# demo.net
KiCad netlist of a schematic drawn in Altium Designer
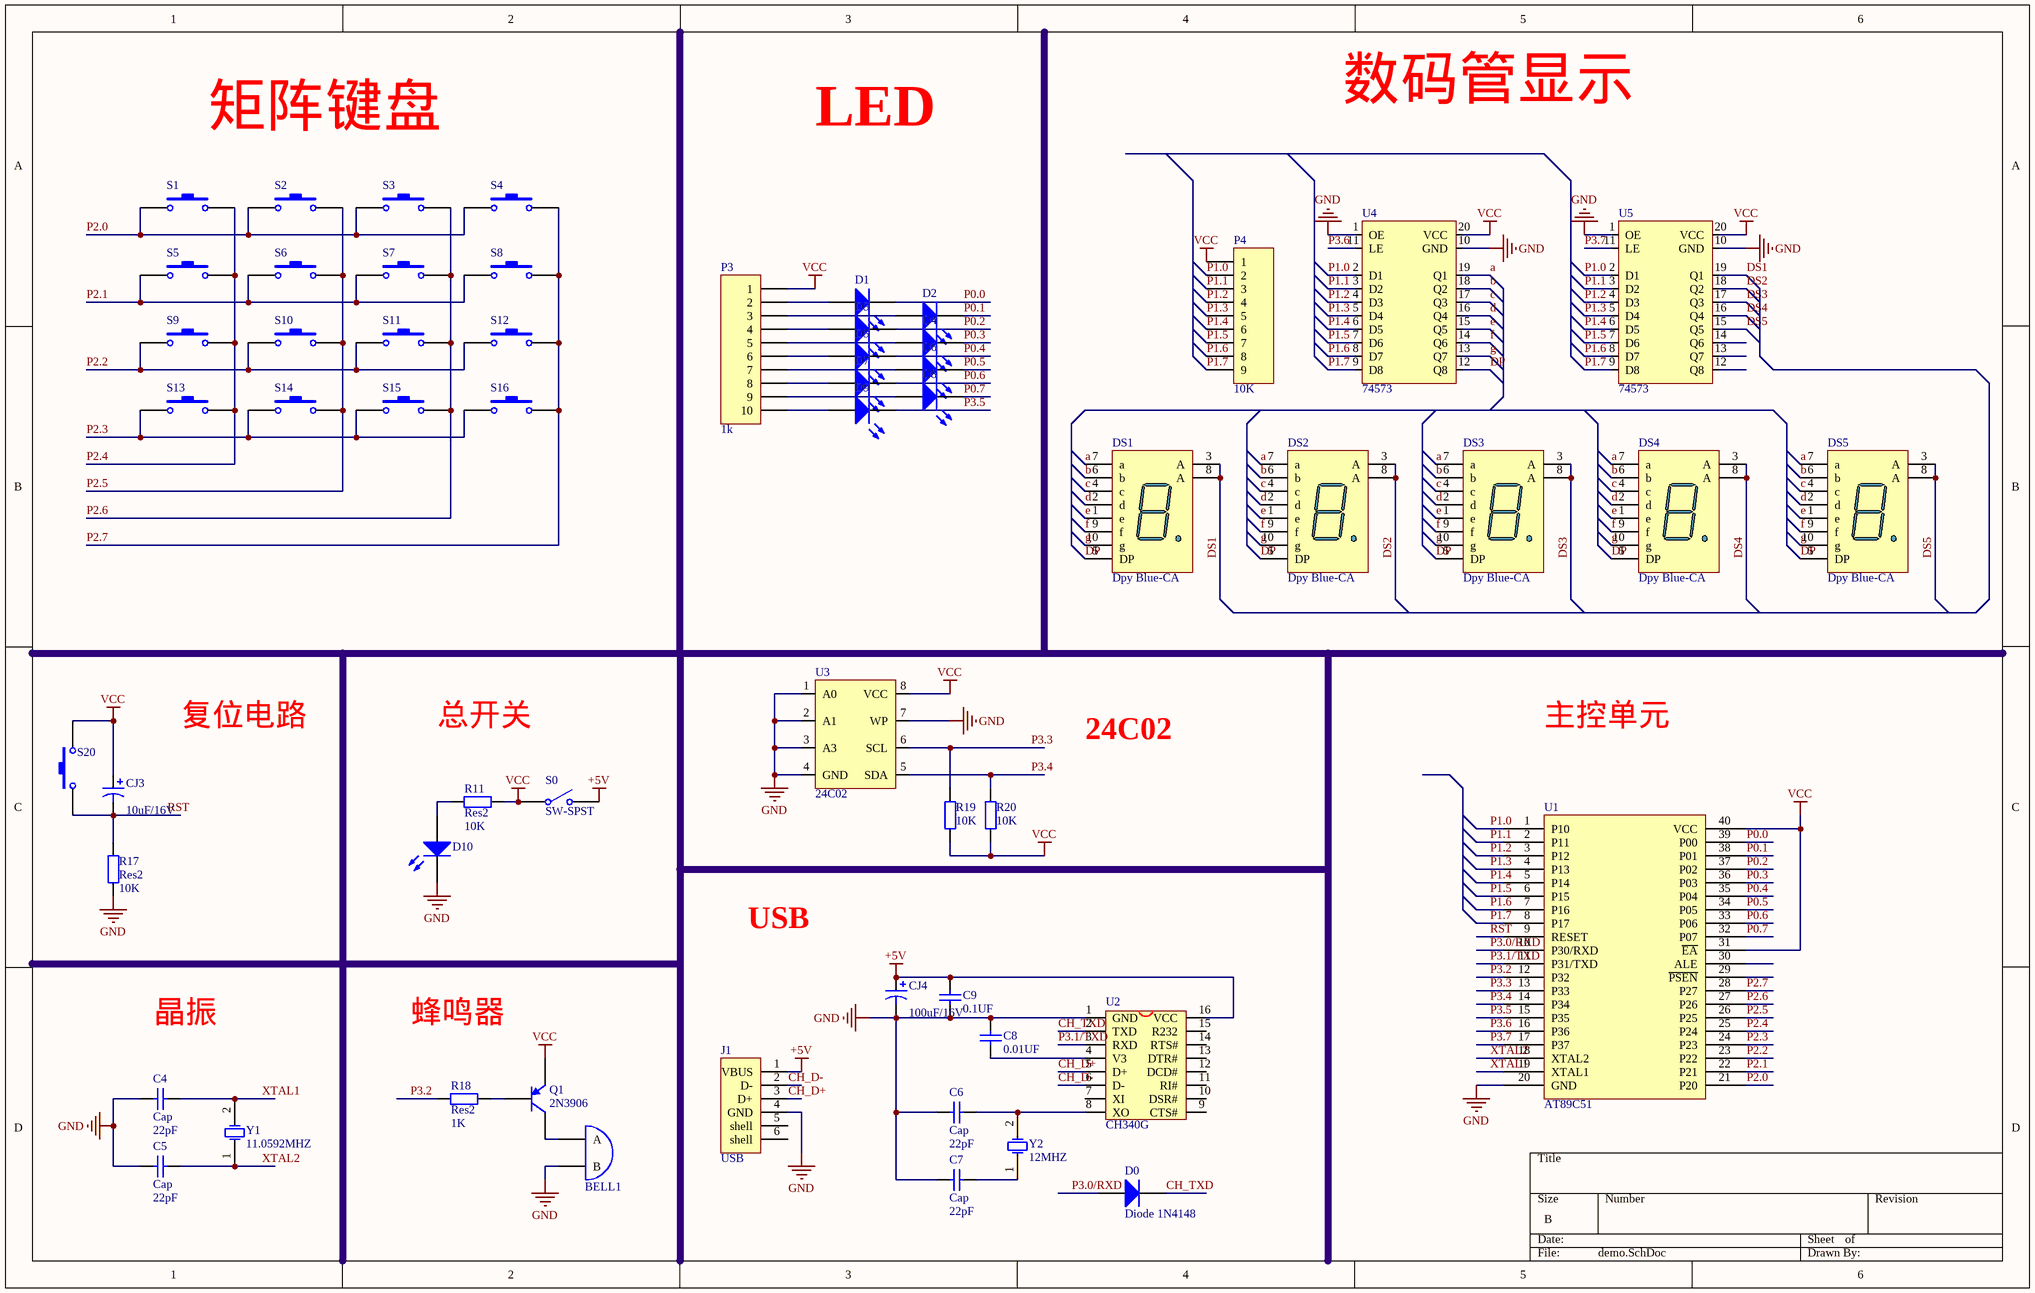
[diagram p0: demo.SchDoc]

(export (version "E")
  (design (tool "Eeschema 10.0.6"))
  (components
    (comp (ref "BELL1") (value "BELL") (footprint "BELL") (libsource (lib "SQ-1") (part "BELL")))
    (comp (ref "C4")
      (value "Cap")
      (footprint "0805C")
      (description "Capacitor")
      (fields (field (name "ALTIUM_VALUE") "22pF") (field (name "PUBLISHER") "Altium Limited"))
      (libsource (lib "Miscellaneous Devices") (part "Cap"))
    )
    (comp (ref "C5")
      (value "Cap")
      (footprint "0805C")
      (description "Capacitor")
      (fields (field (name "ALTIUM_VALUE") "22pF") (field (name "PUBLISHER") "Altium Limited"))
      (libsource (lib "Miscellaneous Devices") (part "Cap"))
    )
    (comp (ref "C6")
      (value "Cap")
      (footprint "0805C")
      (description "Capacitor")
      (fields (field (name "ALTIUM_VALUE") "22pF") (field (name "PUBLISHER") "Altium Limited"))
      (libsource (lib "Miscellaneous Devices") (part "Cap"))
    )
    (comp (ref "C7")
      (value "Cap")
      (footprint "0805C")
      (description "Capacitor")
      (fields (field (name "ALTIUM_VALUE") "22pF") (field (name "PUBLISHER") "Altium Limited"))
      (libsource (lib "Miscellaneous Devices") (part "Cap"))
    )
    (comp (ref "C8")
      (value "0.01UF")
      (footprint "0805C")
      (description "Capacitor")
      (fields (field (name "PUBLISHER") "Altium Limited"))
      (libsource (lib "Miscellaneous Devices") (part "Cap"))
    )
    (comp (ref "C9")
      (value "0.1UF")
      (footprint "0805C")
      (description "Capacitor")
      (fields (field (name "PUBLISHER") "Altium Limited"))
      (libsource (lib "Miscellaneous Devices") (part "Cap"))
    )
    (comp (ref "CJ3")
      (value "10uF/16V")
      (footprint "RB10U")
      (description "Polarized Capacitor (Radial)")
      (fields (field (name "PUBLISHER") "Altium Limited"))
      (libsource (lib "Miscellaneous Devices") (part "Cap Pol1"))
    )
    (comp (ref "CJ4")
      (value "100uF/16V")
      (footprint "RB10U")
      (description "Polarized Capacitor (Radial)")
      (fields (field (name "PUBLISHER") "Altium Limited"))
      (libsource (lib "Miscellaneous Devices") (part "Cap Pol1"))
    )
    (comp (ref "D0")
      (value "Diode 1N4148")
      (footprint "SOD123F")
      (description "High Conductance Fast Diode")
      (fields (field (name "PUBLISHER") "Altium Limited"))
      (libsource (lib "SQ-1") (part "Diode 1N4148"))
    )
    (comp (ref "D1")
      (value "LED0")
      (footprint "0805-LED")
      (description "Typical INFRARED GaAs LED")
      (fields (field (name "PUBLISHER") "Altium Limited"))
      (libsource (lib "Miscellaneous Devices") (part "LED0"))
    )
    (comp (ref "D2")
      (value "LED0")
      (footprint "0805-LED")
      (description "Typical INFRARED GaAs LED")
      (fields (field (name "PUBLISHER") "Altium Limited"))
      (libsource (lib "Miscellaneous Devices") (part "LED0"))
    )
    (comp (ref "D3")
      (value "LED0")
      (footprint "0805-LED")
      (description "Typical INFRARED GaAs LED")
      (fields (field (name "PUBLISHER") "Altium Limited"))
      (libsource (lib "Miscellaneous Devices") (part "LED0"))
    )
    (comp (ref "D4")
      (value "LED0")
      (footprint "0805-LED")
      (description "Typical INFRARED GaAs LED")
      (fields (field (name "PUBLISHER") "Altium Limited"))
      (libsource (lib "Miscellaneous Devices") (part "LED0"))
    )
    (comp (ref "D5")
      (value "LED0")
      (footprint "0805-LED")
      (description "Typical INFRARED GaAs LED")
      (fields (field (name "PUBLISHER") "Altium Limited"))
      (libsource (lib "Miscellaneous Devices") (part "LED0"))
    )
    (comp (ref "D6")
      (value "LED0")
      (footprint "0805-LED")
      (description "Typical INFRARED GaAs LED")
      (fields (field (name "PUBLISHER") "Altium Limited"))
      (libsource (lib "Miscellaneous Devices") (part "LED0"))
    )
    (comp (ref "D7")
      (value "LED0")
      (footprint "0805-LED")
      (description "Typical INFRARED GaAs LED")
      (fields (field (name "PUBLISHER") "Altium Limited"))
      (libsource (lib "Miscellaneous Devices") (part "LED0"))
    )
    (comp (ref "D8")
      (value "LED0")
      (footprint "0805-LED")
      (description "Typical INFRARED GaAs LED")
      (fields (field (name "PUBLISHER") "Altium Limited"))
      (libsource (lib "Miscellaneous Devices") (part "LED0"))
    )
    (comp (ref "D9")
      (value "LED0")
      (footprint "0805-LED")
      (description "Typical INFRARED GaAs LED")
      (fields (field (name "PUBLISHER") "Altium Limited"))
      (libsource (lib "Miscellaneous Devices") (part "LED0"))
    )
    (comp (ref "D10")
      (value "LED0")
      (footprint "0805-LED")
      (description "Typical INFRARED GaAs LED")
      (fields (field (name "PUBLISHER") "Altium Limited"))
      (libsource (lib "Miscellaneous Devices") (part "LED0"))
    )
    (comp (ref "DS1")
      (value "Dpy Blue-CA")
      (footprint "H")
      (description "14.2 mm General Purpose Blue 7-Segment Display: CA, RH DP, Gray Surface")
      (fields (field (name "PUBLISHER") "Altium Limited"))
      (libsource (lib "Miscellaneous Devices") (part "Dpy Blue-CA"))
    )
    (comp (ref "DS2")
      (value "Dpy Blue-CA")
      (footprint "H")
      (description "14.2 mm General Purpose Blue 7-Segment Display: CA, RH DP, Gray Surface")
      (fields (field (name "PUBLISHER") "Altium Limited"))
      (libsource (lib "Miscellaneous Devices") (part "Dpy Blue-CA"))
    )
    (comp (ref "DS3")
      (value "Dpy Blue-CA")
      (footprint "H")
      (description "14.2 mm General Purpose Blue 7-Segment Display: CA, RH DP, Gray Surface")
      (fields (field (name "PUBLISHER") "Altium Limited"))
      (libsource (lib "Miscellaneous Devices") (part "Dpy Blue-CA"))
    )
    (comp (ref "DS4")
      (value "Dpy Blue-CA")
      (footprint "H")
      (description "14.2 mm General Purpose Blue 7-Segment Display: CA, RH DP, Gray Surface")
      (fields (field (name "PUBLISHER") "Altium Limited"))
      (libsource (lib "Miscellaneous Devices") (part "Dpy Blue-CA"))
    )
    (comp (ref "DS5")
      (value "Dpy Blue-CA")
      (footprint "H")
      (description "14.2 mm General Purpose Blue 7-Segment Display: CA, RH DP, Gray Surface")
      (fields (field (name "PUBLISHER") "Altium Limited"))
      (libsource (lib "Miscellaneous Devices") (part "Dpy Blue-CA"))
    )
    (comp (ref "J1") (value "USB") (footprint "USB-B") (libsource (lib "SQ-1") (part "USB")))
    (comp (ref "P3")
      (value "1k")
      (footprint "HDR1X10")
      (description "Header, 10-Pin")
      (fields (field (name "PUBLISHER") "Altium Limited"))
      (libsource (lib "Miscellaneous Connectors") (part "Header 10"))
    )
    (comp (ref "P4")
      (value "10K")
      (footprint "HDR1X9")
      (description "Header, 9-Pin")
      (fields (field (name "PUBLISHER") "Altium Limited"))
      (libsource (lib "Miscellaneous Connectors") (part "Header 9"))
    )
    (comp (ref "Q1")
      (value "2N3906")
      (footprint "TO-92A")
      (description "PNP General Purpose Amplifier")
      (fields (field (name "PUBLISHER") "Altium Limited"))
      (libsource (lib "Miscellaneous Devices") (part "2N3906"))
    )
    (comp (ref "R11")
      (value "Res2")
      (footprint "0805")
      (description "Resistor")
      (fields (field (name "ALTIUM_VALUE") "10K") (field (name "PUBLISHER") "Altium Limited"))
      (libsource (lib "") (part "Res2_1"))
    )
    (comp (ref "R17")
      (value "Res2")
      (footprint "0805")
      (description "Resistor")
      (fields (field (name "ALTIUM_VALUE") "10K") (field (name "PUBLISHER") "Altium Limited"))
      (libsource (lib "") (part "Res2_2"))
    )
    (comp (ref "R18")
      (value "Res2")
      (footprint "0805")
      (description "Resistor")
      (fields (field (name "ALTIUM_VALUE") "1K") (field (name "PUBLISHER") "Altium Limited"))
      (libsource (lib "") (part "Res2_1"))
    )
    (comp (ref "R19")
      (value "10K")
      (footprint "0805")
      (description "Resistor")
      (fields (field (name "PUBLISHER") "Altium Limited"))
      (libsource (lib "Miscellaneous Devices") (part "Res2"))
    )
    (comp (ref "R20")
      (value "10K")
      (footprint "0805")
      (description "Resistor")
      (fields (field (name "PUBLISHER") "Altium Limited"))
      (libsource (lib "Miscellaneous Devices") (part "Res2"))
    )
    (comp (ref "S0")
      (value "SW-SPST")
      (footprint "SWD")
      (description "Single-Pole, Single-Throw Switch")
      (fields (field (name "PUBLISHER") "Altium Limited"))
      (libsource (lib "Miscellaneous Devices") (part "SW-SPST"))
    )
    (comp (ref "S1")
      (value "~")
      (footprint "SWD")
      (description "Switch")
      (fields (field (name "PUBLISHER") "Altium Limited"))
      (libsource (lib "Miscellaneous Devices") (part "SW-PB"))
    )
    (comp (ref "S2")
      (value "~")
      (footprint "SWD")
      (description "Switch")
      (fields (field (name "PUBLISHER") "Altium Limited"))
      (libsource (lib "Miscellaneous Devices") (part "SW-PB"))
    )
    (comp (ref "S3")
      (value "~")
      (footprint "SWD")
      (description "Switch")
      (fields (field (name "PUBLISHER") "Altium Limited"))
      (libsource (lib "Miscellaneous Devices") (part "SW-PB"))
    )
    (comp (ref "S4")
      (value "~")
      (footprint "SWD")
      (description "Switch")
      (fields (field (name "PUBLISHER") "Altium Limited"))
      (libsource (lib "Miscellaneous Devices") (part "SW-PB"))
    )
    (comp (ref "S5")
      (value "~")
      (footprint "SWD")
      (description "Switch")
      (fields (field (name "PUBLISHER") "Altium Limited"))
      (libsource (lib "Miscellaneous Devices") (part "SW-PB"))
    )
    (comp (ref "S6")
      (value "~")
      (footprint "SWD")
      (description "Switch")
      (fields (field (name "PUBLISHER") "Altium Limited"))
      (libsource (lib "Miscellaneous Devices") (part "SW-PB"))
    )
    (comp (ref "S7")
      (value "~")
      (footprint "SWD")
      (description "Switch")
      (fields (field (name "PUBLISHER") "Altium Limited"))
      (libsource (lib "Miscellaneous Devices") (part "SW-PB"))
    )
    (comp (ref "S8")
      (value "~")
      (footprint "SWD")
      (description "Switch")
      (fields (field (name "PUBLISHER") "Altium Limited"))
      (libsource (lib "Miscellaneous Devices") (part "SW-PB"))
    )
    (comp (ref "S9")
      (value "~")
      (footprint "SWD")
      (description "Switch")
      (fields (field (name "PUBLISHER") "Altium Limited"))
      (libsource (lib "Miscellaneous Devices") (part "SW-PB"))
    )
    (comp (ref "S10")
      (value "~")
      (footprint "SWD")
      (description "Switch")
      (fields (field (name "PUBLISHER") "Altium Limited"))
      (libsource (lib "Miscellaneous Devices") (part "SW-PB"))
    )
    (comp (ref "S11")
      (value "~")
      (footprint "SWD")
      (description "Switch")
      (fields (field (name "PUBLISHER") "Altium Limited"))
      (libsource (lib "Miscellaneous Devices") (part "SW-PB"))
    )
    (comp (ref "S12")
      (value "~")
      (footprint "SWD")
      (description "Switch")
      (fields (field (name "PUBLISHER") "Altium Limited"))
      (libsource (lib "Miscellaneous Devices") (part "SW-PB"))
    )
    (comp (ref "S13")
      (value "~")
      (footprint "SWD")
      (description "Switch")
      (fields (field (name "PUBLISHER") "Altium Limited"))
      (libsource (lib "Miscellaneous Devices") (part "SW-PB"))
    )
    (comp (ref "S14")
      (value "~")
      (footprint "SWD")
      (description "Switch")
      (fields (field (name "PUBLISHER") "Altium Limited"))
      (libsource (lib "Miscellaneous Devices") (part "SW-PB"))
    )
    (comp (ref "S15")
      (value "~")
      (footprint "SWD")
      (description "Switch")
      (fields (field (name "PUBLISHER") "Altium Limited"))
      (libsource (lib "Miscellaneous Devices") (part "SW-PB"))
    )
    (comp (ref "S16")
      (value "~")
      (footprint "SWD")
      (description "Switch")
      (fields (field (name "PUBLISHER") "Altium Limited"))
      (libsource (lib "Miscellaneous Devices") (part "SW-PB"))
    )
    (comp (ref "S20")
      (value "~")
      (footprint "SWD")
      (description "Switch")
      (fields (field (name "PUBLISHER") "Altium Limited"))
      (libsource (lib "Miscellaneous Devices") (part "SW-PB"))
    )
    (comp (ref "U1") (value "AT89C51") (footprint "DIP40紧锁座") (libsource (lib "SQ-1") (part "AT89C51")))
    (comp (ref "U2")
      (value "CH340G")
      (footprint "SO-16")
      (description "USB2UART")
      (libsource (lib "SQ-1") (part "CH340G"))
    )
    (comp (ref "U3") (value "24C02") (footprint "SOP-8") (libsource (lib "SQ-1") (part "24C02")))
    (comp (ref "U4") (value "74573") (footprint "SO20W") (libsource (lib "SQ-1") (part "74573")))
    (comp (ref "U5") (value "74573") (footprint "SO20W") (libsource (lib "SQ-1") (part "74573")))
    (comp (ref "Y1")
      (value "11.0592MHZ")
      (footprint "XTAL")
      (description "Crystal Oscillator")
      (fields (field (name "PUBLISHER") "Altium Limited"))
      (libsource (lib "Miscellaneous Devices") (part "XTAL"))
    )
    (comp (ref "Y2")
      (value "12MHZ")
      (footprint "XTAL")
      (description "Crystal Oscillator")
      (fields (field (name "PUBLISHER") "Altium Limited"))
      (libsource (lib "Miscellaneous Devices") (part "XTAL"))
    )
  )
  (nets
    (net (code "1") (name "+5V") (class "Default")
      (node (ref "C9") (pin "2") (pinfunction "2_2") (pintype "passive"))
      (node (ref "CJ4") (pin "1") (pinfunction "1_1") (pintype "passive"))
      (node (ref "J1") (pin "1") (pinfunction "VBUS_1") (pintype "passive"))
      (node (ref "S0") (pin "2") (pinfunction "NO_2") (pintype "passive"))
      (node (ref "U2") (pin "16") (pinfunction "VCC_16") (pintype "passive"))
    )
    (net (code "2") (name "/CH_D+") (class "Default")
      (node (ref "J1") (pin "3") (pinfunction "D+_3") (pintype "passive"))
      (node (ref "U2") (pin "5") (pinfunction "D+_5") (pintype "passive"))
    )
    (net (code "3") (name "/CH_D-") (class "Default")
      (node (ref "J1") (pin "2") (pinfunction "D-_2") (pintype "passive"))
      (node (ref "U2") (pin "6") (pinfunction "D-_6") (pintype "passive"))
    )
    (net (code "4") (name "/CH_TXD") (class "Default")
      (node (ref "D0") (pin "2") (pinfunction "K_2") (pintype "passive"))
      (node (ref "U2") (pin "2") (pinfunction "TXD_2") (pintype "passive"))
    )
    (net (code "5") (name "/DP") (class "Default")
      (node (ref "DS1") (pin "5") (pinfunction "DP_5") (pintype "passive"))
      (node (ref "DS2") (pin "5") (pinfunction "DP_5") (pintype "passive"))
      (node (ref "DS3") (pin "5") (pinfunction "DP_5") (pintype "passive"))
      (node (ref "DS4") (pin "5") (pinfunction "DP_5") (pintype "passive"))
      (node (ref "DS5") (pin "5") (pinfunction "DP_5") (pintype "passive"))
      (node (ref "U4") (pin "12") (pinfunction "Q8_12") (pintype "passive"))
    )
    (net (code "6") (name "/DS1") (class "Default")
      (node (ref "DS1") (pin "3") (pinfunction "A_3") (pintype "passive"))
      (node (ref "DS1") (pin "8") (pinfunction "A_8") (pintype "passive"))
      (node (ref "U5") (pin "19") (pinfunction "Q1_19") (pintype "passive"))
    )
    (net (code "7") (name "/DS2") (class "Default")
      (node (ref "DS2") (pin "3") (pinfunction "A_3") (pintype "passive"))
      (node (ref "DS2") (pin "8") (pinfunction "A_8") (pintype "passive"))
      (node (ref "U5") (pin "18") (pinfunction "Q2_18") (pintype "passive"))
    )
    (net (code "8") (name "/DS3") (class "Default")
      (node (ref "DS3") (pin "3") (pinfunction "A_3") (pintype "passive"))
      (node (ref "DS3") (pin "8") (pinfunction "A_8") (pintype "passive"))
      (node (ref "U5") (pin "17") (pinfunction "Q3_17") (pintype "passive"))
    )
    (net (code "9") (name "/DS4") (class "Default")
      (node (ref "DS4") (pin "3") (pinfunction "A_3") (pintype "passive"))
      (node (ref "DS4") (pin "8") (pinfunction "A_8") (pintype "passive"))
      (node (ref "U5") (pin "16") (pinfunction "Q4_16") (pintype "passive"))
    )
    (net (code "10") (name "/DS5") (class "Default")
      (node (ref "DS5") (pin "3") (pinfunction "A_3") (pintype "passive"))
      (node (ref "DS5") (pin "8") (pinfunction "A_8") (pintype "passive"))
      (node (ref "U5") (pin "15") (pinfunction "Q5_15") (pintype "passive"))
    )
    (net (code "11") (name "/P0.0") (class "Default")
      (node (ref "D1") (pin "2") (pinfunction "K_2") (pintype "passive"))
      (node (ref "U1") (pin "39") (pinfunction "P00_39") (pintype "passive"))
    )
    (net (code "12") (name "/P0.1") (class "Default")
      (node (ref "D2") (pin "2") (pinfunction "K_2") (pintype "passive"))
      (node (ref "U1") (pin "38") (pinfunction "P01_38") (pintype "passive"))
    )
    (net (code "13") (name "/P0.2") (class "Default")
      (node (ref "D3") (pin "2") (pinfunction "K_2") (pintype "passive"))
      (node (ref "U1") (pin "37") (pinfunction "P02_37") (pintype "passive"))
    )
    (net (code "14") (name "/P0.3") (class "Default")
      (node (ref "D4") (pin "2") (pinfunction "K_2") (pintype "passive"))
      (node (ref "U1") (pin "36") (pinfunction "P03_36") (pintype "passive"))
    )
    (net (code "15") (name "/P0.4") (class "Default")
      (node (ref "D5") (pin "2") (pinfunction "K_2") (pintype "passive"))
      (node (ref "U1") (pin "35") (pinfunction "P04_35") (pintype "passive"))
    )
    (net (code "16") (name "/P0.5") (class "Default")
      (node (ref "D6") (pin "2") (pinfunction "K_2") (pintype "passive"))
      (node (ref "U1") (pin "34") (pinfunction "P05_34") (pintype "passive"))
    )
    (net (code "17") (name "/P0.6") (class "Default")
      (node (ref "D7") (pin "2") (pinfunction "K_2") (pintype "passive"))
      (node (ref "U1") (pin "33") (pinfunction "P06_33") (pintype "passive"))
    )
    (net (code "18") (name "/P0.7") (class "Default")
      (node (ref "D8") (pin "2") (pinfunction "K_2") (pintype "passive"))
      (node (ref "U1") (pin "32") (pinfunction "P07_32") (pintype "passive"))
    )
    (net (code "19") (name "/P1.0") (class "Default")
      (node (ref "P4") (pin "2") (pinfunction "2_2") (pintype "passive"))
      (node (ref "U1") (pin "1") (pinfunction "P10_1") (pintype "passive"))
      (node (ref "U4") (pin "2") (pinfunction "D1_2") (pintype "passive"))
      (node (ref "U5") (pin "2") (pinfunction "D1_2") (pintype "passive"))
    )
    (net (code "20") (name "/P1.1") (class "Default")
      (node (ref "P4") (pin "3") (pinfunction "3_3") (pintype "passive"))
      (node (ref "U1") (pin "2") (pinfunction "P11_2") (pintype "passive"))
      (node (ref "U4") (pin "3") (pinfunction "D2_3") (pintype "passive"))
      (node (ref "U5") (pin "3") (pinfunction "D2_3") (pintype "passive"))
    )
    (net (code "21") (name "/P1.2") (class "Default")
      (node (ref "P4") (pin "4") (pinfunction "4_4") (pintype "passive"))
      (node (ref "U1") (pin "3") (pinfunction "P12_3") (pintype "passive"))
      (node (ref "U4") (pin "4") (pinfunction "D3_4") (pintype "passive"))
      (node (ref "U5") (pin "4") (pinfunction "D3_4") (pintype "passive"))
    )
    (net (code "22") (name "/P1.3") (class "Default")
      (node (ref "P4") (pin "5") (pinfunction "5_5") (pintype "passive"))
      (node (ref "U1") (pin "4") (pinfunction "P13_4") (pintype "passive"))
      (node (ref "U4") (pin "5") (pinfunction "D4_5") (pintype "passive"))
      (node (ref "U5") (pin "5") (pinfunction "D4_5") (pintype "passive"))
    )
    (net (code "23") (name "/P1.4") (class "Default")
      (node (ref "P4") (pin "6") (pinfunction "6_6") (pintype "passive"))
      (node (ref "U1") (pin "5") (pinfunction "P14_5") (pintype "passive"))
      (node (ref "U4") (pin "6") (pinfunction "D5_6") (pintype "passive"))
      (node (ref "U5") (pin "6") (pinfunction "D5_6") (pintype "passive"))
    )
    (net (code "24") (name "/P1.5") (class "Default")
      (node (ref "P4") (pin "7") (pinfunction "7_7") (pintype "passive"))
      (node (ref "U1") (pin "6") (pinfunction "P15_6") (pintype "passive"))
      (node (ref "U4") (pin "7") (pinfunction "D6_7") (pintype "passive"))
      (node (ref "U5") (pin "7") (pinfunction "D6_7") (pintype "passive"))
    )
    (net (code "25") (name "/P1.6") (class "Default")
      (node (ref "P4") (pin "8") (pinfunction "8_8") (pintype "passive"))
      (node (ref "U1") (pin "7") (pinfunction "P16_7") (pintype "passive"))
      (node (ref "U4") (pin "8") (pinfunction "D7_8") (pintype "passive"))
      (node (ref "U5") (pin "8") (pinfunction "D7_8") (pintype "passive"))
    )
    (net (code "26") (name "/P1.7") (class "Default")
      (node (ref "P4") (pin "9") (pinfunction "9_9") (pintype "passive"))
      (node (ref "U1") (pin "8") (pinfunction "P17_8") (pintype "passive"))
      (node (ref "U4") (pin "9") (pinfunction "D8_9") (pintype "passive"))
      (node (ref "U5") (pin "9") (pinfunction "D8_9") (pintype "passive"))
    )
    (net (code "27") (name "/P2.0") (class "Default")
      (node (ref "S1") (pin "1") (pinfunction "1_1") (pintype "passive"))
      (node (ref "S2") (pin "1") (pinfunction "1_1") (pintype "passive"))
      (node (ref "S3") (pin "1") (pinfunction "1_1") (pintype "passive"))
      (node (ref "S4") (pin "1") (pinfunction "1_1") (pintype "passive"))
      (node (ref "U1") (pin "21") (pinfunction "P20_21") (pintype "passive"))
    )
    (net (code "28") (name "/P2.1") (class "Default")
      (node (ref "S5") (pin "1") (pinfunction "1_1") (pintype "passive"))
      (node (ref "S6") (pin "1") (pinfunction "1_1") (pintype "passive"))
      (node (ref "S7") (pin "1") (pinfunction "1_1") (pintype "passive"))
      (node (ref "S8") (pin "1") (pinfunction "1_1") (pintype "passive"))
      (node (ref "U1") (pin "22") (pinfunction "P21_22") (pintype "passive"))
    )
    (net (code "29") (name "/P2.2") (class "Default")
      (node (ref "S10") (pin "1") (pinfunction "1_1") (pintype "passive"))
      (node (ref "S11") (pin "1") (pinfunction "1_1") (pintype "passive"))
      (node (ref "S12") (pin "1") (pinfunction "1_1") (pintype "passive"))
      (node (ref "S9") (pin "1") (pinfunction "1_1") (pintype "passive"))
      (node (ref "U1") (pin "23") (pinfunction "P22_23") (pintype "passive"))
    )
    (net (code "30") (name "/P2.3") (class "Default")
      (node (ref "S13") (pin "1") (pinfunction "1_1") (pintype "passive"))
      (node (ref "S14") (pin "1") (pinfunction "1_1") (pintype "passive"))
      (node (ref "S15") (pin "1") (pinfunction "1_1") (pintype "passive"))
      (node (ref "S16") (pin "1") (pinfunction "1_1") (pintype "passive"))
      (node (ref "U1") (pin "24") (pinfunction "P23_24") (pintype "passive"))
    )
    (net (code "31") (name "/P2.4") (class "Default")
      (node (ref "S1") (pin "2") (pinfunction "2_2") (pintype "passive"))
      (node (ref "S13") (pin "2") (pinfunction "2_2") (pintype "passive"))
      (node (ref "S5") (pin "2") (pinfunction "2_2") (pintype "passive"))
      (node (ref "S9") (pin "2") (pinfunction "2_2") (pintype "passive"))
      (node (ref "U1") (pin "25") (pinfunction "P24_25") (pintype "passive"))
    )
    (net (code "32") (name "/P2.5") (class "Default")
      (node (ref "S10") (pin "2") (pinfunction "2_2") (pintype "passive"))
      (node (ref "S14") (pin "2") (pinfunction "2_2") (pintype "passive"))
      (node (ref "S2") (pin "2") (pinfunction "2_2") (pintype "passive"))
      (node (ref "S6") (pin "2") (pinfunction "2_2") (pintype "passive"))
      (node (ref "U1") (pin "26") (pinfunction "P25_26") (pintype "passive"))
    )
    (net (code "33") (name "/P2.6") (class "Default")
      (node (ref "S11") (pin "2") (pinfunction "2_2") (pintype "passive"))
      (node (ref "S15") (pin "2") (pinfunction "2_2") (pintype "passive"))
      (node (ref "S3") (pin "2") (pinfunction "2_2") (pintype "passive"))
      (node (ref "S7") (pin "2") (pinfunction "2_2") (pintype "passive"))
      (node (ref "U1") (pin "27") (pinfunction "P26_27") (pintype "passive"))
    )
    (net (code "34") (name "/P2.7") (class "Default")
      (node (ref "S12") (pin "2") (pinfunction "2_2") (pintype "passive"))
      (node (ref "S16") (pin "2") (pinfunction "2_2") (pintype "passive"))
      (node (ref "S4") (pin "2") (pinfunction "2_2") (pintype "passive"))
      (node (ref "S8") (pin "2") (pinfunction "2_2") (pintype "passive"))
      (node (ref "U1") (pin "28") (pinfunction "P27_28") (pintype "passive"))
    )
    (net (code "35") (name "/P3.0{slash}RXD") (class "Default")
      (node (ref "D0") (pin "1") (pinfunction "A_1") (pintype "passive"))
      (node (ref "U1") (pin "10") (pinfunction "P30/RXD_10") (pintype "passive"))
    )
    (net (code "36") (name "/P3.1{slash}TXD") (class "Default")
      (node (ref "U1") (pin "11") (pinfunction "P31/TXD_11") (pintype "passive"))
      (node (ref "U2") (pin "3") (pinfunction "RXD_3") (pintype "passive"))
    )
    (net (code "37") (name "/P3.2") (class "Default")
      (node (ref "R18") (pin "2") (pinfunction "2_2") (pintype "passive"))
      (node (ref "U1") (pin "12") (pinfunction "P32_12") (pintype "passive"))
    )
    (net (code "38") (name "/P3.3") (class "Default")
      (node (ref "R19") (pin "1") (pinfunction "1_1") (pintype "passive"))
      (node (ref "U1") (pin "13") (pinfunction "P33_13") (pintype "passive"))
      (node (ref "U3") (pin "6") (pinfunction "SCL_6") (pintype "passive"))
    )
    (net (code "39") (name "/P3.4") (class "Default")
      (node (ref "R20") (pin "1") (pinfunction "1_1") (pintype "passive"))
      (node (ref "U1") (pin "14") (pinfunction "P34_14") (pintype "passive"))
      (node (ref "U3") (pin "5") (pinfunction "SDA_5") (pintype "passive"))
    )
    (net (code "40") (name "/P3.5") (class "Default")
      (node (ref "D9") (pin "2") (pinfunction "K_2") (pintype "passive"))
      (node (ref "U1") (pin "15") (pinfunction "P35_15") (pintype "passive"))
    )
    (net (code "41") (name "/P3.6") (class "Default")
      (node (ref "U1") (pin "16") (pinfunction "P36_16") (pintype "passive"))
      (node (ref "U4") (pin "11") (pinfunction "LE_11") (pintype "passive"))
    )
    (net (code "42") (name "/P3.7") (class "Default")
      (node (ref "U1") (pin "17") (pinfunction "P37_17") (pintype "passive"))
      (node (ref "U5") (pin "11") (pinfunction "LE_11") (pintype "passive"))
    )
    (net (code "43") (name "/RST") (class "Default")
      (node (ref "CJ3") (pin "2") (pinfunction "2_2") (pintype "passive"))
      (node (ref "R17") (pin "2") (pinfunction "2_2") (pintype "passive"))
      (node (ref "S20") (pin "1") (pinfunction "1_1") (pintype "passive"))
      (node (ref "U1") (pin "9") (pinfunction "RESET_9") (pintype "passive"))
    )
    (net (code "44") (name "/XTAL1") (class "Default")
      (node (ref "C4") (pin "2") (pinfunction "2_2") (pintype "passive"))
      (node (ref "U1") (pin "19") (pinfunction "XTAL1_19") (pintype "passive"))
      (node (ref "Y1") (pin "2") (pinfunction "OSC2_2") (pintype "passive"))
    )
    (net (code "45") (name "/XTAL2") (class "Default")
      (node (ref "C5") (pin "2") (pinfunction "2_2") (pintype "passive"))
      (node (ref "U1") (pin "18") (pinfunction "XTAL2_18") (pintype "passive"))
      (node (ref "Y1") (pin "1") (pinfunction "OSC1_1") (pintype "passive"))
    )
    (net (code "46") (name "/a") (class "Default")
      (node (ref "DS1") (pin "7") (pinfunction "a_7") (pintype "passive"))
      (node (ref "DS2") (pin "7") (pinfunction "a_7") (pintype "passive"))
      (node (ref "DS3") (pin "7") (pinfunction "a_7") (pintype "passive"))
      (node (ref "DS4") (pin "7") (pinfunction "a_7") (pintype "passive"))
      (node (ref "DS5") (pin "7") (pinfunction "a_7") (pintype "passive"))
      (node (ref "U4") (pin "19") (pinfunction "Q1_19") (pintype "passive"))
    )
    (net (code "47") (name "/b") (class "Default")
      (node (ref "DS1") (pin "6") (pinfunction "b_6") (pintype "passive"))
      (node (ref "DS2") (pin "6") (pinfunction "b_6") (pintype "passive"))
      (node (ref "DS3") (pin "6") (pinfunction "b_6") (pintype "passive"))
      (node (ref "DS4") (pin "6") (pinfunction "b_6") (pintype "passive"))
      (node (ref "DS5") (pin "6") (pinfunction "b_6") (pintype "passive"))
      (node (ref "U4") (pin "18") (pinfunction "Q2_18") (pintype "passive"))
    )
    (net (code "48") (name "/c") (class "Default")
      (node (ref "DS1") (pin "4") (pinfunction "c_4") (pintype "passive"))
      (node (ref "DS2") (pin "4") (pinfunction "c_4") (pintype "passive"))
      (node (ref "DS3") (pin "4") (pinfunction "c_4") (pintype "passive"))
      (node (ref "DS4") (pin "4") (pinfunction "c_4") (pintype "passive"))
      (node (ref "DS5") (pin "4") (pinfunction "c_4") (pintype "passive"))
      (node (ref "U4") (pin "17") (pinfunction "Q3_17") (pintype "passive"))
    )
    (net (code "49") (name "/d") (class "Default")
      (node (ref "DS1") (pin "2") (pinfunction "d_2") (pintype "passive"))
      (node (ref "DS2") (pin "2") (pinfunction "d_2") (pintype "passive"))
      (node (ref "DS3") (pin "2") (pinfunction "d_2") (pintype "passive"))
      (node (ref "DS4") (pin "2") (pinfunction "d_2") (pintype "passive"))
      (node (ref "DS5") (pin "2") (pinfunction "d_2") (pintype "passive"))
      (node (ref "U4") (pin "16") (pinfunction "Q4_16") (pintype "passive"))
    )
    (net (code "50") (name "/e") (class "Default")
      (node (ref "DS1") (pin "1") (pinfunction "e_1") (pintype "passive"))
      (node (ref "DS2") (pin "1") (pinfunction "e_1") (pintype "passive"))
      (node (ref "DS3") (pin "1") (pinfunction "e_1") (pintype "passive"))
      (node (ref "DS4") (pin "1") (pinfunction "e_1") (pintype "passive"))
      (node (ref "DS5") (pin "1") (pinfunction "e_1") (pintype "passive"))
      (node (ref "U4") (pin "15") (pinfunction "Q5_15") (pintype "passive"))
    )
    (net (code "51") (name "/f") (class "Default")
      (node (ref "DS1") (pin "9") (pinfunction "f_9") (pintype "passive"))
      (node (ref "DS2") (pin "9") (pinfunction "f_9") (pintype "passive"))
      (node (ref "DS3") (pin "9") (pinfunction "f_9") (pintype "passive"))
      (node (ref "DS4") (pin "9") (pinfunction "f_9") (pintype "passive"))
      (node (ref "DS5") (pin "9") (pinfunction "f_9") (pintype "passive"))
      (node (ref "U4") (pin "14") (pinfunction "Q6_14") (pintype "passive"))
    )
    (net (code "52") (name "/g") (class "Default")
      (node (ref "DS1") (pin "10") (pinfunction "g_10") (pintype "passive"))
      (node (ref "DS2") (pin "10") (pinfunction "g_10") (pintype "passive"))
      (node (ref "DS3") (pin "10") (pinfunction "g_10") (pintype "passive"))
      (node (ref "DS4") (pin "10") (pinfunction "g_10") (pintype "passive"))
      (node (ref "DS5") (pin "10") (pinfunction "g_10") (pintype "passive"))
      (node (ref "U4") (pin "13") (pinfunction "Q7_13") (pintype "passive"))
    )
    (net (code "53") (name "GND") (class "Default")
      (node (ref "BELL1") (pin "2") (pinfunction "B_2") (pintype "passive"))
      (node (ref "C4") (pin "1") (pinfunction "1_1") (pintype "passive"))
      (node (ref "C5") (pin "1") (pinfunction "1_1") (pintype "passive"))
      (node (ref "C6") (pin "1") (pinfunction "1_1") (pintype "passive"))
      (node (ref "C7") (pin "1") (pinfunction "1_1") (pintype "passive"))
      (node (ref "C8") (pin "2") (pinfunction "2_2") (pintype "passive"))
      (node (ref "C9") (pin "1") (pinfunction "1_1") (pintype "passive"))
      (node (ref "CJ4") (pin "2") (pinfunction "2_2") (pintype "passive"))
      (node (ref "D10") (pin "2") (pinfunction "K_2") (pintype "passive"))
      (node (ref "J1") (pin "4") (pinfunction "GND_4") (pintype "passive"))
      (node (ref "R17") (pin "1") (pinfunction "1_1") (pintype "passive"))
      (node (ref "U1") (pin "20") (pinfunction "GND_20") (pintype "passive"))
      (node (ref "U2") (pin "1") (pinfunction "GND_1") (pintype "passive"))
      (node (ref "U3") (pin "1") (pinfunction "A0_1") (pintype "passive"))
      (node (ref "U3") (pin "2") (pinfunction "A1_2") (pintype "passive"))
      (node (ref "U3") (pin "3") (pinfunction "A3_3") (pintype "passive"))
      (node (ref "U3") (pin "4") (pinfunction "GND_4") (pintype "passive"))
      (node (ref "U3") (pin "7") (pinfunction "WP_7") (pintype "passive"))
      (node (ref "U4") (pin "1") (pinfunction "OE_1") (pintype "passive"))
      (node (ref "U4") (pin "10") (pinfunction "GND_10") (pintype "passive"))
      (node (ref "U5") (pin "1") (pinfunction "OE_1") (pintype "passive"))
      (node (ref "U5") (pin "10") (pinfunction "GND_10") (pintype "passive"))
    )
    (net (code "54") (name "Net-(BELL1-A)") (class "Default")
      (node (ref "BELL1") (pin "1") (pinfunction "A_1") (pintype "passive"))
      (node (ref "Q1") (pin "3") (pinfunction "C_3") (pintype "passive"))
    )
    (net (code "55") (name "Net-(D1-A)") (class "Default")
      (node (ref "D1") (pin "1") (pinfunction "A_1") (pintype "passive"))
      (node (ref "P3") (pin "2") (pinfunction "2_2") (pintype "passive"))
    )
    (net (code "56") (name "Net-(D2-A)") (class "Default")
      (node (ref "D2") (pin "1") (pinfunction "A_1") (pintype "passive"))
      (node (ref "P3") (pin "3") (pinfunction "3_3") (pintype "passive"))
    )
    (net (code "57") (name "Net-(D3-A)") (class "Default")
      (node (ref "D3") (pin "1") (pinfunction "A_1") (pintype "passive"))
      (node (ref "P3") (pin "4") (pinfunction "4_4") (pintype "passive"))
    )
    (net (code "58") (name "Net-(D4-A)") (class "Default")
      (node (ref "D4") (pin "1") (pinfunction "A_1") (pintype "passive"))
      (node (ref "P3") (pin "5") (pinfunction "5_5") (pintype "passive"))
    )
    (net (code "59") (name "Net-(D5-A)") (class "Default")
      (node (ref "D5") (pin "1") (pinfunction "A_1") (pintype "passive"))
      (node (ref "P3") (pin "6") (pinfunction "6_6") (pintype "passive"))
    )
    (net (code "60") (name "Net-(D6-A)") (class "Default")
      (node (ref "D6") (pin "1") (pinfunction "A_1") (pintype "passive"))
      (node (ref "P3") (pin "7") (pinfunction "7_7") (pintype "passive"))
    )
    (net (code "61") (name "Net-(D7-A)") (class "Default")
      (node (ref "D7") (pin "1") (pinfunction "A_1") (pintype "passive"))
      (node (ref "P3") (pin "8") (pinfunction "8_8") (pintype "passive"))
    )
    (net (code "62") (name "Net-(D8-A)") (class "Default")
      (node (ref "D8") (pin "1") (pinfunction "A_1") (pintype "passive"))
      (node (ref "P3") (pin "9") (pinfunction "9_9") (pintype "passive"))
    )
    (net (code "63") (name "Net-(D9-A)") (class "Default")
      (node (ref "D9") (pin "1") (pinfunction "A_1") (pintype "passive"))
      (node (ref "P3") (pin "10") (pinfunction "10_10") (pintype "passive"))
    )
    (net (code "64") (name "Net-(D10-A)") (class "Default")
      (node (ref "D10") (pin "1") (pinfunction "A_1") (pintype "passive"))
      (node (ref "R11") (pin "2") (pinfunction "2_2") (pintype "passive"))
    )
    (net (code "65") (name "Net-(Q1-B)") (class "Default")
      (node (ref "Q1") (pin "2") (pinfunction "B_2") (pintype "passive"))
      (node (ref "R18") (pin "1") (pinfunction "1_1") (pintype "passive"))
    )
    (net (code "66") (name "Net-(U2-V3)") (class "Default")
      (node (ref "C8") (pin "1") (pinfunction "1_1") (pintype "passive"))
      (node (ref "U2") (pin "4") (pinfunction "V3_4") (pintype "passive"))
    )
    (net (code "67") (name "Net-(U2-XO)") (class "Default")
      (node (ref "C6") (pin "2") (pinfunction "2_2") (pintype "passive"))
      (node (ref "U2") (pin "8") (pinfunction "XO_8") (pintype "passive"))
      (node (ref "Y2") (pin "2") (pinfunction "OSC2_2") (pintype "passive"))
    )
    (net (code "68") (name "Net-(Y2-OSC1)") (class "Default")
      (node (ref "C7") (pin "2") (pinfunction "2_2") (pintype "passive"))
      (node (ref "Y2") (pin "1") (pinfunction "OSC1_1") (pintype "passive"))
    )
    (net (code "69") (name "VCC") (class "Default")
      (node (ref "CJ3") (pin "1") (pinfunction "1_1") (pintype "passive"))
      (node (ref "P3") (pin "1") (pinfunction "1_1") (pintype "passive"))
      (node (ref "P4") (pin "1") (pinfunction "1_1") (pintype "passive"))
      (node (ref "Q1") (pin "1") (pinfunction "E_1") (pintype "passive"))
      (node (ref "R11") (pin "1") (pinfunction "1_1") (pintype "passive"))
      (node (ref "R19") (pin "2") (pinfunction "2_2") (pintype "passive"))
      (node (ref "R20") (pin "2") (pinfunction "2_2") (pintype "passive"))
      (node (ref "S0") (pin "1") (pinfunction "COMMON_1") (pintype "passive"))
      (node (ref "S20") (pin "2") (pinfunction "2_2") (pintype "passive"))
      (node (ref "U1") (pin "31") (pinfunction "~{EA}_31") (pintype "passive"))
      (node (ref "U1") (pin "40") (pinfunction "VCC_40") (pintype "passive"))
      (node (ref "U3") (pin "8") (pinfunction "VCC_8") (pintype "passive"))
      (node (ref "U4") (pin "20") (pinfunction "VCC_20") (pintype "passive"))
      (node (ref "U5") (pin "20") (pinfunction "VCC_20") (pintype "passive"))
    )
    (net (code "70") (name "unconnected-(J1-shell-Pad5)") (class "Default")
      (node (ref "J1") (pin "5") (pinfunction "shell_5") (pintype "passive"))
    )
    (net (code "71") (name "unconnected-(J1-shell-Pad6)") (class "Default")
      (node (ref "J1") (pin "6") (pinfunction "shell_6") (pintype "passive"))
    )
    (net (code "72") (name "unconnected-(U1-ALE-Pad30)") (class "Default")
      (node (ref "U1") (pin "30") (pinfunction "ALE_30") (pintype "passive"))
    )
    (net (code "73") (name "unconnected-(U1-~{PSEN}-Pad29)") (class "Default")
      (node (ref "U1") (pin "29") (pinfunction "~{PSEN}_29") (pintype "passive"))
    )
    (net (code "74") (name "unconnected-(U2-CTS#-Pad9)") (class "Default")
      (node (ref "U2") (pin "9") (pinfunction "CTS#_9") (pintype "passive"))
    )
    (net (code "75") (name "unconnected-(U2-DCD#-Pad12)") (class "Default")
      (node (ref "U2") (pin "12") (pinfunction "DCD#_12") (pintype "passive"))
    )
    (net (code "76") (name "unconnected-(U2-DSR#-Pad10)") (class "Default")
      (node (ref "U2") (pin "10") (pinfunction "DSR#_10") (pintype "passive"))
    )
    (net (code "77") (name "unconnected-(U2-DTR#-Pad13)") (class "Default")
      (node (ref "U2") (pin "13") (pinfunction "DTR#_13") (pintype "passive"))
    )
    (net (code "78") (name "unconnected-(U2-R232-Pad15)") (class "Default")
      (node (ref "U2") (pin "15") (pinfunction "R232_15") (pintype "passive"))
    )
    (net (code "79") (name "unconnected-(U2-RI#-Pad11)") (class "Default")
      (node (ref "U2") (pin "11") (pinfunction "RI#_11") (pintype "passive"))
    )
    (net (code "80") (name "unconnected-(U2-RTS#-Pad14)") (class "Default")
      (node (ref "U2") (pin "14") (pinfunction "RTS#_14") (pintype "passive"))
    )
    (net (code "81") (name "unconnected-(U2-XI-Pad7)") (class "Default")
      (node (ref "U2") (pin "7") (pinfunction "XI_7") (pintype "passive"))
    )
    (net (code "82") (name "unconnected-(U5-Q6-Pad14)") (class "Default")
      (node (ref "U5") (pin "14") (pinfunction "Q6_14") (pintype "passive"))
    )
    (net (code "83") (name "unconnected-(U5-Q7-Pad13)") (class "Default")
      (node (ref "U5") (pin "13") (pinfunction "Q7_13") (pintype "passive"))
    )
    (net (code "84") (name "unconnected-(U5-Q8-Pad12)") (class "Default")
      (node (ref "U5") (pin "12") (pinfunction "Q8_12") (pintype "passive"))
    )
  )
)
